# CONNECTOR.net
KiCad netlist of a schematic drawn in Altium Designer
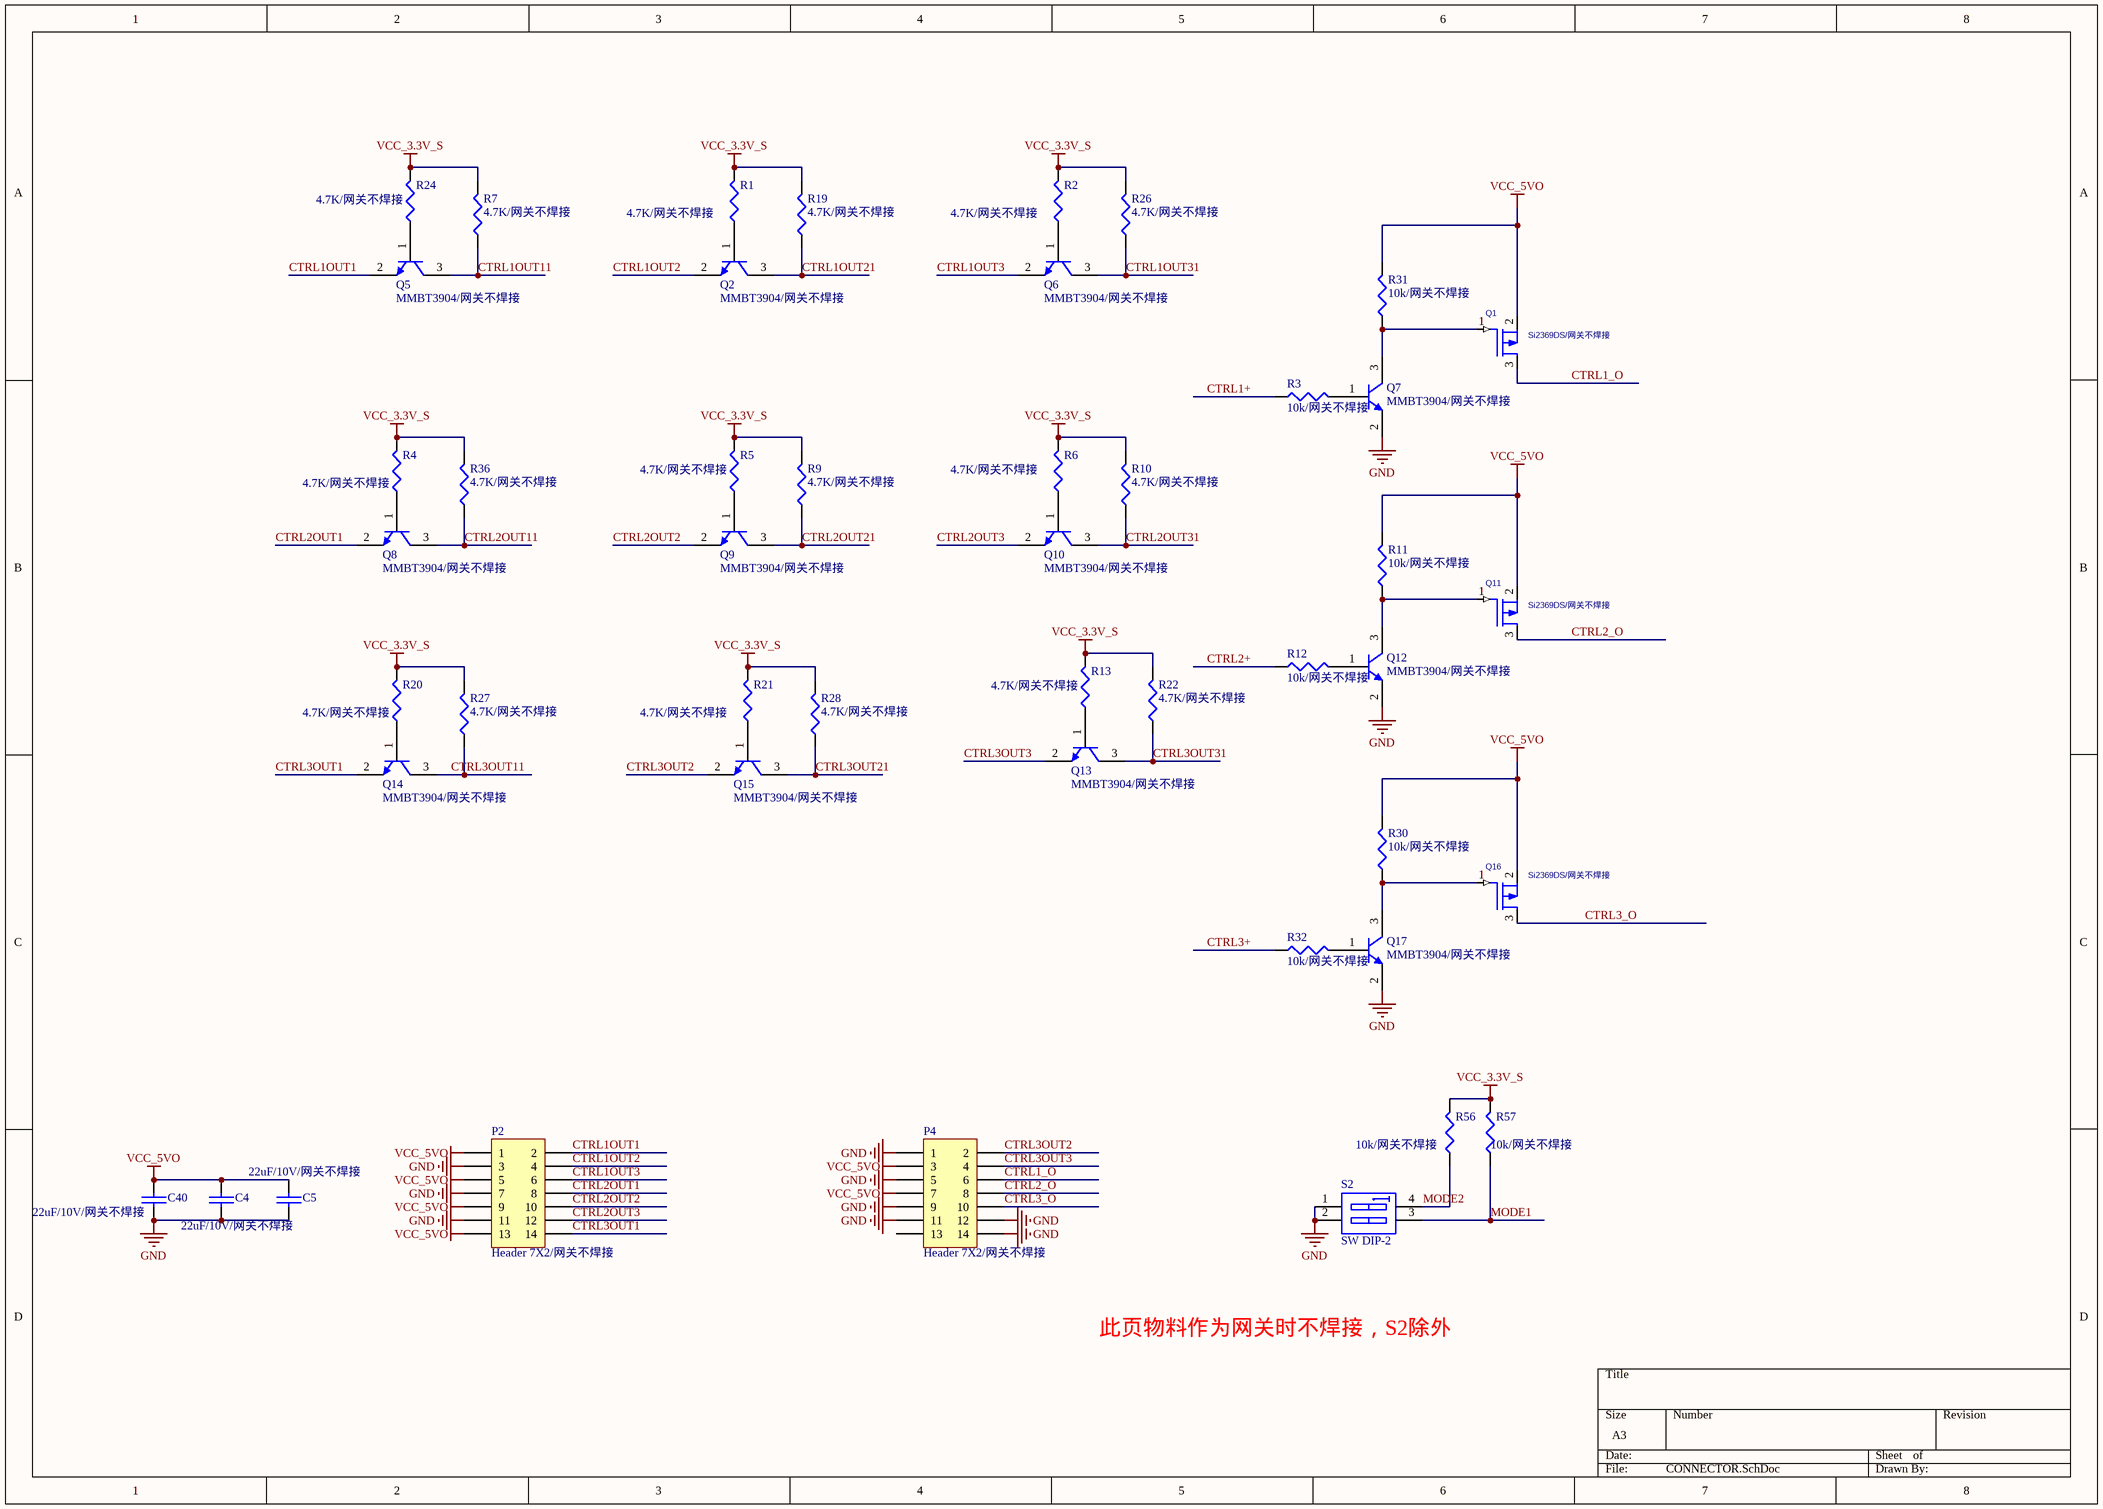
[diagram p0: CONNECTOR.SchDoc]

(export (version "E")
  (design (tool "Eeschema 10.0.6"))
  (components
    (comp (ref "C4")
      (value "22uF/10V/网关不焊接")
      (footprint "1206C")
      (description "Capacitor")
      (libsource (lib "ZWLIntegrated_Library") (part "CAP"))
    )
    (comp (ref "C5")
      (value "22uF/10V/网关不焊接")
      (footprint "1206C")
      (description "Capacitor")
      (libsource (lib "ZWLIntegrated_Library") (part "CAP"))
    )
    (comp (ref "C40")
      (value "22uF/10V/网关不焊接")
      (footprint "1206C")
      (description "Capacitor")
      (libsource (lib "ZWLIntegrated_Library") (part "CAP"))
    )
    (comp (ref "P2")
      (value "Header 7X2/网关不焊接")
      (footprint "14X2.54MMZ")
      (description "Header, 7-Pin, Dual row")
      (fields (field (name "PUBLISHER") "Altium Limited"))
      (libsource (lib "Miscellaneous Connectors") (part "Header 7X2"))
    )
    (comp (ref "P4")
      (value "Header 7X2/网关不焊接")
      (footprint "14X2.54MMZ")
      (description "Header, 7-Pin, Dual row")
      (fields (field (name "PUBLISHER") "Altium Limited"))
      (libsource (lib "Miscellaneous Connectors") (part "Header 7X2"))
    )
    (comp (ref "Q1") (value "Si2369DS/网关不焊接") (footprint "SOT23") (libsource (lib "*") (part "MOSFET P_1")))
    (comp (ref "Q2") (value "MMBT3904/网关不焊接") (footprint "SOT23-3") (libsource (lib "Schlib1") (part "NPN")))
    (comp (ref "Q5") (value "MMBT3904/网关不焊接") (footprint "SOT23-3") (libsource (lib "Schlib1") (part "NPN")))
    (comp (ref "Q6") (value "MMBT3904/网关不焊接") (footprint "SOT23-3") (libsource (lib "Schlib1") (part "NPN")))
    (comp (ref "Q7") (value "MMBT3904/网关不焊接") (footprint "SOT23-3") (libsource (lib "Schlib1") (part "NPN")))
    (comp (ref "Q8") (value "MMBT3904/网关不焊接") (footprint "SOT23-3") (libsource (lib "Schlib1") (part "NPN")))
    (comp (ref "Q9") (value "MMBT3904/网关不焊接") (footprint "SOT23-3") (libsource (lib "Schlib1") (part "NPN")))
    (comp (ref "Q10") (value "MMBT3904/网关不焊接") (footprint "SOT23-3") (libsource (lib "Schlib1") (part "NPN")))
    (comp (ref "Q11") (value "Si2369DS/网关不焊接") (footprint "SOT23") (libsource (lib "*") (part "MOSFET P_1")))
    (comp (ref "Q12") (value "MMBT3904/网关不焊接") (footprint "SOT23-3") (libsource (lib "Schlib1") (part "NPN")))
    (comp (ref "Q13") (value "MMBT3904/网关不焊接") (footprint "SOT23-3") (libsource (lib "Schlib1") (part "NPN")))
    (comp (ref "Q14") (value "MMBT3904/网关不焊接") (footprint "SOT23-3") (libsource (lib "Schlib1") (part "NPN")))
    (comp (ref "Q15") (value "MMBT3904/网关不焊接") (footprint "SOT23-3") (libsource (lib "Schlib1") (part "NPN")))
    (comp (ref "Q16") (value "Si2369DS/网关不焊接") (footprint "SOT23") (libsource (lib "*") (part "MOSFET P_1")))
    (comp (ref "Q17") (value "MMBT3904/网关不焊接") (footprint "SOT23-3") (libsource (lib "Schlib1") (part "NPN")))
    (comp (ref "R1")
      (value "4.7K/网关不焊接")
      (footprint "0603R")
      (libsource (lib "ZWLIntegrated_Library") (part "RES1"))
    )
    (comp (ref "R2")
      (value "4.7K/网关不焊接")
      (footprint "0603R")
      (libsource (lib "ZWLIntegrated_Library") (part "RES1"))
    )
    (comp (ref "R3")
      (value "10k/网关不焊接")
      (footprint "0603R")
      (libsource (lib "ZWLIntegrated_Library") (part "RES1"))
    )
    (comp (ref "R4")
      (value "4.7K/网关不焊接")
      (footprint "0603R")
      (libsource (lib "ZWLIntegrated_Library") (part "RES1"))
    )
    (comp (ref "R5")
      (value "4.7K/网关不焊接")
      (footprint "0603R")
      (libsource (lib "ZWLIntegrated_Library") (part "RES1"))
    )
    (comp (ref "R6")
      (value "4.7K/网关不焊接")
      (footprint "0603R")
      (libsource (lib "ZWLIntegrated_Library") (part "RES1"))
    )
    (comp (ref "R7")
      (value "4.7K/网关不焊接")
      (footprint "0603R")
      (libsource (lib "ZWLIntegrated_Library") (part "RES1"))
    )
    (comp (ref "R9")
      (value "4.7K/网关不焊接")
      (footprint "0603R")
      (libsource (lib "ZWLIntegrated_Library") (part "RES1"))
    )
    (comp (ref "R10")
      (value "4.7K/网关不焊接")
      (footprint "0603R")
      (libsource (lib "ZWLIntegrated_Library") (part "RES1"))
    )
    (comp (ref "R11")
      (value "10k/网关不焊接")
      (footprint "0603R")
      (libsource (lib "ZWLIntegrated_Library") (part "RES1"))
    )
    (comp (ref "R12")
      (value "10k/网关不焊接")
      (footprint "0603R")
      (libsource (lib "ZWLIntegrated_Library") (part "RES1"))
    )
    (comp (ref "R13")
      (value "4.7K/网关不焊接")
      (footprint "0603R")
      (libsource (lib "ZWLIntegrated_Library") (part "RES1"))
    )
    (comp (ref "R19")
      (value "4.7K/网关不焊接")
      (footprint "0603R")
      (libsource (lib "ZWLIntegrated_Library") (part "RES1"))
    )
    (comp (ref "R20")
      (value "4.7K/网关不焊接")
      (footprint "0603R")
      (libsource (lib "ZWLIntegrated_Library") (part "RES1"))
    )
    (comp (ref "R21")
      (value "4.7K/网关不焊接")
      (footprint "0603R")
      (libsource (lib "ZWLIntegrated_Library") (part "RES1"))
    )
    (comp (ref "R22")
      (value "4.7K/网关不焊接")
      (footprint "0603R")
      (libsource (lib "ZWLIntegrated_Library") (part "RES1"))
    )
    (comp (ref "R24")
      (value "4.7K/网关不焊接")
      (footprint "0603R")
      (libsource (lib "ZWLIntegrated_Library") (part "RES1"))
    )
    (comp (ref "R26")
      (value "4.7K/网关不焊接")
      (footprint "0603R")
      (libsource (lib "ZWLIntegrated_Library") (part "RES1"))
    )
    (comp (ref "R27")
      (value "4.7K/网关不焊接")
      (footprint "0603R")
      (libsource (lib "ZWLIntegrated_Library") (part "RES1"))
    )
    (comp (ref "R28")
      (value "4.7K/网关不焊接")
      (footprint "0603R")
      (libsource (lib "ZWLIntegrated_Library") (part "RES1"))
    )
    (comp (ref "R30")
      (value "10k/网关不焊接")
      (footprint "0603R")
      (libsource (lib "ZWLIntegrated_Library") (part "RES1"))
    )
    (comp (ref "R31")
      (value "10k/网关不焊接")
      (footprint "0603R")
      (libsource (lib "ZWLIntegrated_Library") (part "RES1"))
    )
    (comp (ref "R32")
      (value "10k/网关不焊接")
      (footprint "0603R")
      (libsource (lib "ZWLIntegrated_Library") (part "RES1"))
    )
    (comp (ref "R36")
      (value "4.7K/网关不焊接")
      (footprint "0603R")
      (libsource (lib "ZWLIntegrated_Library") (part "RES1"))
    )
    (comp (ref "R56")
      (value "10k/网关不焊接")
      (footprint "0603R")
      (libsource (lib "ZWLIntegrated_Library") (part "RES1"))
    )
    (comp (ref "R57")
      (value "10k/网关不焊接")
      (footprint "0603R")
      (libsource (lib "ZWLIntegrated_Library") (part "RES1"))
    )
    (comp (ref "S2")
      (value "SW DIP-2")
      (footprint "SW_SMT_4")
      (description "DIP Switch, 2 Position, SPST")
      (fields (field (name "PUBLISHER") "Altium Limited"))
      (libsource (lib "Miscellaneous Devices") (part "SW DIP-2"))
    )
  )
  (nets
    (net (code "1") (name "/CTRL1+") (class "Default")
      (node (ref "R3") (pin "1") (pinfunction "1_1") (pintype "passive"))
    )
    (net (code "2") (name "/CTRL1OUT1") (class "Default")
      (node (ref "P2") (pin "2") (pinfunction "2_2") (pintype "passive"))
      (node (ref "Q5") (pin "2") (pinfunction "E_2") (pintype "passive"))
    )
    (net (code "3") (name "/CTRL1OUT2") (class "Default")
      (node (ref "P2") (pin "4") (pinfunction "4_4") (pintype "passive"))
      (node (ref "Q2") (pin "2") (pinfunction "E_2") (pintype "passive"))
    )
    (net (code "4") (name "/CTRL1OUT3") (class "Default")
      (node (ref "P2") (pin "6") (pinfunction "6_6") (pintype "passive"))
      (node (ref "Q6") (pin "2") (pinfunction "E_2") (pintype "passive"))
    )
    (net (code "5") (name "/CTRL1OUT11") (class "Default")
      (node (ref "Q5") (pin "3") (pinfunction "C_3") (pintype "passive"))
      (node (ref "R7") (pin "1") (pinfunction "1_1") (pintype "passive"))
    )
    (net (code "6") (name "/CTRL1OUT21") (class "Default")
      (node (ref "Q2") (pin "3") (pinfunction "C_3") (pintype "passive"))
      (node (ref "R19") (pin "1") (pinfunction "1_1") (pintype "passive"))
    )
    (net (code "7") (name "/CTRL1OUT31") (class "Default")
      (node (ref "Q6") (pin "3") (pinfunction "C_3") (pintype "passive"))
      (node (ref "R26") (pin "1") (pinfunction "1_1") (pintype "passive"))
    )
    (net (code "8") (name "/CTRL1_O") (class "Default")
      (node (ref "P4") (pin "6") (pinfunction "6_6") (pintype "passive"))
      (node (ref "Q1") (pin "3") (pinfunction "SOURCE_3") (pintype "passive"))
    )
    (net (code "9") (name "/CTRL2+") (class "Default")
      (node (ref "R12") (pin "1") (pinfunction "1_1") (pintype "passive"))
    )
    (net (code "10") (name "/CTRL2OUT1") (class "Default")
      (node (ref "P2") (pin "8") (pinfunction "8_8") (pintype "passive"))
      (node (ref "Q8") (pin "2") (pinfunction "E_2") (pintype "passive"))
    )
    (net (code "11") (name "/CTRL2OUT2") (class "Default")
      (node (ref "P2") (pin "10") (pinfunction "10_10") (pintype "passive"))
      (node (ref "Q9") (pin "2") (pinfunction "E_2") (pintype "passive"))
    )
    (net (code "12") (name "/CTRL2OUT3") (class "Default")
      (node (ref "P2") (pin "12") (pinfunction "12_12") (pintype "passive"))
      (node (ref "Q10") (pin "2") (pinfunction "E_2") (pintype "passive"))
    )
    (net (code "13") (name "/CTRL2OUT11") (class "Default")
      (node (ref "Q8") (pin "3") (pinfunction "C_3") (pintype "passive"))
      (node (ref "R36") (pin "1") (pinfunction "1_1") (pintype "passive"))
    )
    (net (code "14") (name "/CTRL2OUT21") (class "Default")
      (node (ref "Q9") (pin "3") (pinfunction "C_3") (pintype "passive"))
      (node (ref "R9") (pin "1") (pinfunction "1_1") (pintype "passive"))
    )
    (net (code "15") (name "/CTRL2OUT31") (class "Default")
      (node (ref "Q10") (pin "3") (pinfunction "C_3") (pintype "passive"))
      (node (ref "R10") (pin "1") (pinfunction "1_1") (pintype "passive"))
    )
    (net (code "16") (name "/CTRL2_O") (class "Default")
      (node (ref "P4") (pin "8") (pinfunction "8_8") (pintype "passive"))
      (node (ref "Q11") (pin "3") (pinfunction "SOURCE_3") (pintype "passive"))
    )
    (net (code "17") (name "/CTRL3+") (class "Default")
      (node (ref "R32") (pin "1") (pinfunction "1_1") (pintype "passive"))
    )
    (net (code "18") (name "/CTRL3OUT1") (class "Default")
      (node (ref "P2") (pin "14") (pinfunction "14_14") (pintype "passive"))
      (node (ref "Q14") (pin "2") (pinfunction "E_2") (pintype "passive"))
    )
    (net (code "19") (name "/CTRL3OUT2") (class "Default")
      (node (ref "P4") (pin "2") (pinfunction "2_2") (pintype "passive"))
      (node (ref "Q15") (pin "2") (pinfunction "E_2") (pintype "passive"))
    )
    (net (code "20") (name "/CTRL3OUT3") (class "Default")
      (node (ref "P4") (pin "4") (pinfunction "4_4") (pintype "passive"))
      (node (ref "Q13") (pin "2") (pinfunction "E_2") (pintype "passive"))
    )
    (net (code "21") (name "/CTRL3OUT11") (class "Default")
      (node (ref "Q14") (pin "3") (pinfunction "C_3") (pintype "passive"))
      (node (ref "R27") (pin "1") (pinfunction "1_1") (pintype "passive"))
    )
    (net (code "22") (name "/CTRL3OUT21") (class "Default")
      (node (ref "Q15") (pin "3") (pinfunction "C_3") (pintype "passive"))
      (node (ref "R28") (pin "1") (pinfunction "1_1") (pintype "passive"))
    )
    (net (code "23") (name "/CTRL3OUT31") (class "Default")
      (node (ref "Q13") (pin "3") (pinfunction "C_3") (pintype "passive"))
      (node (ref "R22") (pin "1") (pinfunction "1_1") (pintype "passive"))
    )
    (net (code "24") (name "/CTRL3_O") (class "Default")
      (node (ref "P4") (pin "10") (pinfunction "10_10") (pintype "passive"))
      (node (ref "Q16") (pin "3") (pinfunction "SOURCE_3") (pintype "passive"))
    )
    (net (code "25") (name "/MODE1") (class "Default")
      (node (ref "R57") (pin "1") (pinfunction "1_1") (pintype "passive"))
      (node (ref "S2") (pin "3") (pinfunction "B2_3") (pintype "passive"))
    )
    (net (code "26") (name "/MODE2") (class "Default")
      (node (ref "R56") (pin "1") (pinfunction "1_1") (pintype "passive"))
      (node (ref "S2") (pin "4") (pinfunction "B1_4") (pintype "passive"))
    )
    (net (code "27") (name "GND") (class "Default")
      (node (ref "C4") (pin "2") (pinfunction "2_2") (pintype "passive"))
      (node (ref "C40") (pin "2") (pinfunction "2_2") (pintype "passive"))
      (node (ref "C5") (pin "2") (pinfunction "2_2") (pintype "passive"))
      (node (ref "P2") (pin "11") (pinfunction "11_11") (pintype "passive"))
      (node (ref "P2") (pin "3") (pinfunction "3_3") (pintype "passive"))
      (node (ref "P2") (pin "7") (pinfunction "7_7") (pintype "passive"))
      (node (ref "P4") (pin "1") (pinfunction "1_1") (pintype "passive"))
      (node (ref "P4") (pin "11") (pinfunction "11_11") (pintype "passive"))
      (node (ref "P4") (pin "12") (pinfunction "12_12") (pintype "passive"))
      (node (ref "P4") (pin "14") (pinfunction "14_14") (pintype "passive"))
      (node (ref "P4") (pin "5") (pinfunction "5_5") (pintype "passive"))
      (node (ref "P4") (pin "9") (pinfunction "9_9") (pintype "passive"))
      (node (ref "Q12") (pin "2") (pinfunction "E_2") (pintype "passive"))
      (node (ref "Q17") (pin "2") (pinfunction "E_2") (pintype "passive"))
      (node (ref "Q7") (pin "2") (pinfunction "E_2") (pintype "passive"))
      (node (ref "S2") (pin "1") (pinfunction "A1_1") (pintype "passive"))
      (node (ref "S2") (pin "2") (pinfunction "A2_2") (pintype "passive"))
    )
    (net (code "28") (name "Net-(Q1-GATE)") (class "Default")
      (node (ref "Q1") (pin "1") (pinfunction "GATE_1") (pintype "input"))
      (node (ref "Q7") (pin "3") (pinfunction "C_3") (pintype "passive"))
      (node (ref "R31") (pin "1") (pinfunction "1_1") (pintype "passive"))
    )
    (net (code "29") (name "Net-(Q2-B)") (class "Default")
      (node (ref "Q2") (pin "1") (pinfunction "B_1") (pintype "passive"))
      (node (ref "R1") (pin "1") (pinfunction "1_1") (pintype "passive"))
    )
    (net (code "30") (name "Net-(Q5-B)") (class "Default")
      (node (ref "Q5") (pin "1") (pinfunction "B_1") (pintype "passive"))
      (node (ref "R24") (pin "1") (pinfunction "1_1") (pintype "passive"))
    )
    (net (code "31") (name "Net-(Q6-B)") (class "Default")
      (node (ref "Q6") (pin "1") (pinfunction "B_1") (pintype "passive"))
      (node (ref "R2") (pin "1") (pinfunction "1_1") (pintype "passive"))
    )
    (net (code "32") (name "Net-(Q7-B)") (class "Default")
      (node (ref "Q7") (pin "1") (pinfunction "B_1") (pintype "passive"))
      (node (ref "R3") (pin "2") (pinfunction "2_2") (pintype "passive"))
    )
    (net (code "33") (name "Net-(Q8-B)") (class "Default")
      (node (ref "Q8") (pin "1") (pinfunction "B_1") (pintype "passive"))
      (node (ref "R4") (pin "1") (pinfunction "1_1") (pintype "passive"))
    )
    (net (code "34") (name "Net-(Q9-B)") (class "Default")
      (node (ref "Q9") (pin "1") (pinfunction "B_1") (pintype "passive"))
      (node (ref "R5") (pin "1") (pinfunction "1_1") (pintype "passive"))
    )
    (net (code "35") (name "Net-(Q10-B)") (class "Default")
      (node (ref "Q10") (pin "1") (pinfunction "B_1") (pintype "passive"))
      (node (ref "R6") (pin "1") (pinfunction "1_1") (pintype "passive"))
    )
    (net (code "36") (name "Net-(Q11-GATE)") (class "Default")
      (node (ref "Q11") (pin "1") (pinfunction "GATE_1") (pintype "input"))
      (node (ref "Q12") (pin "3") (pinfunction "C_3") (pintype "passive"))
      (node (ref "R11") (pin "1") (pinfunction "1_1") (pintype "passive"))
    )
    (net (code "37") (name "Net-(Q12-B)") (class "Default")
      (node (ref "Q12") (pin "1") (pinfunction "B_1") (pintype "passive"))
      (node (ref "R12") (pin "2") (pinfunction "2_2") (pintype "passive"))
    )
    (net (code "38") (name "Net-(Q13-B)") (class "Default")
      (node (ref "Q13") (pin "1") (pinfunction "B_1") (pintype "passive"))
      (node (ref "R13") (pin "1") (pinfunction "1_1") (pintype "passive"))
    )
    (net (code "39") (name "Net-(Q14-B)") (class "Default")
      (node (ref "Q14") (pin "1") (pinfunction "B_1") (pintype "passive"))
      (node (ref "R20") (pin "1") (pinfunction "1_1") (pintype "passive"))
    )
    (net (code "40") (name "Net-(Q15-B)") (class "Default")
      (node (ref "Q15") (pin "1") (pinfunction "B_1") (pintype "passive"))
      (node (ref "R21") (pin "1") (pinfunction "1_1") (pintype "passive"))
    )
    (net (code "41") (name "Net-(Q16-GATE)") (class "Default")
      (node (ref "Q16") (pin "1") (pinfunction "GATE_1") (pintype "input"))
      (node (ref "Q17") (pin "3") (pinfunction "C_3") (pintype "passive"))
      (node (ref "R30") (pin "1") (pinfunction "1_1") (pintype "passive"))
    )
    (net (code "42") (name "Net-(Q17-B)") (class "Default")
      (node (ref "Q17") (pin "1") (pinfunction "B_1") (pintype "passive"))
      (node (ref "R32") (pin "2") (pinfunction "2_2") (pintype "passive"))
    )
    (net (code "43") (name "VCC_3.3V_S") (class "Default")
      (node (ref "R1") (pin "2") (pinfunction "2_2") (pintype "passive"))
      (node (ref "R10") (pin "2") (pinfunction "2_2") (pintype "passive"))
      (node (ref "R13") (pin "2") (pinfunction "2_2") (pintype "passive"))
      (node (ref "R19") (pin "2") (pinfunction "2_2") (pintype "passive"))
      (node (ref "R2") (pin "2") (pinfunction "2_2") (pintype "passive"))
      (node (ref "R20") (pin "2") (pinfunction "2_2") (pintype "passive"))
      (node (ref "R21") (pin "2") (pinfunction "2_2") (pintype "passive"))
      (node (ref "R22") (pin "2") (pinfunction "2_2") (pintype "passive"))
      (node (ref "R24") (pin "2") (pinfunction "2_2") (pintype "passive"))
      (node (ref "R26") (pin "2") (pinfunction "2_2") (pintype "passive"))
      (node (ref "R27") (pin "2") (pinfunction "2_2") (pintype "passive"))
      (node (ref "R28") (pin "2") (pinfunction "2_2") (pintype "passive"))
      (node (ref "R36") (pin "2") (pinfunction "2_2") (pintype "passive"))
      (node (ref "R4") (pin "2") (pinfunction "2_2") (pintype "passive"))
      (node (ref "R5") (pin "2") (pinfunction "2_2") (pintype "passive"))
      (node (ref "R56") (pin "2") (pinfunction "2_2") (pintype "passive"))
      (node (ref "R57") (pin "2") (pinfunction "2_2") (pintype "passive"))
      (node (ref "R6") (pin "2") (pinfunction "2_2") (pintype "passive"))
      (node (ref "R7") (pin "2") (pinfunction "2_2") (pintype "passive"))
      (node (ref "R9") (pin "2") (pinfunction "2_2") (pintype "passive"))
    )
    (net (code "44") (name "VCC_5VO") (class "Default")
      (node (ref "C4") (pin "1") (pinfunction "1_1") (pintype "passive"))
      (node (ref "C40") (pin "1") (pinfunction "1_1") (pintype "passive"))
      (node (ref "C5") (pin "1") (pinfunction "1_1") (pintype "passive"))
      (node (ref "P2") (pin "1") (pinfunction "1_1") (pintype "passive"))
      (node (ref "P2") (pin "13") (pinfunction "13_13") (pintype "passive"))
      (node (ref "P2") (pin "5") (pinfunction "5_5") (pintype "passive"))
      (node (ref "P2") (pin "9") (pinfunction "9_9") (pintype "passive"))
      (node (ref "P4") (pin "3") (pinfunction "3_3") (pintype "passive"))
      (node (ref "P4") (pin "7") (pinfunction "7_7") (pintype "passive"))
      (node (ref "Q1") (pin "2") (pinfunction "DRAIN_2") (pintype "passive"))
      (node (ref "Q11") (pin "2") (pinfunction "DRAIN_2") (pintype "passive"))
      (node (ref "Q16") (pin "2") (pinfunction "DRAIN_2") (pintype "passive"))
      (node (ref "R11") (pin "2") (pinfunction "2_2") (pintype "passive"))
      (node (ref "R30") (pin "2") (pinfunction "2_2") (pintype "passive"))
      (node (ref "R31") (pin "2") (pinfunction "2_2") (pintype "passive"))
    )
    (net (code "45") (name "unconnected-(P4-Pad13)") (class "Default")
      (node (ref "P4") (pin "13") (pinfunction "13_13") (pintype "passive"))
    )
  )
)
